# FluxR3-v3.net
KiCad netlist of a schematic drawn in EAGLE
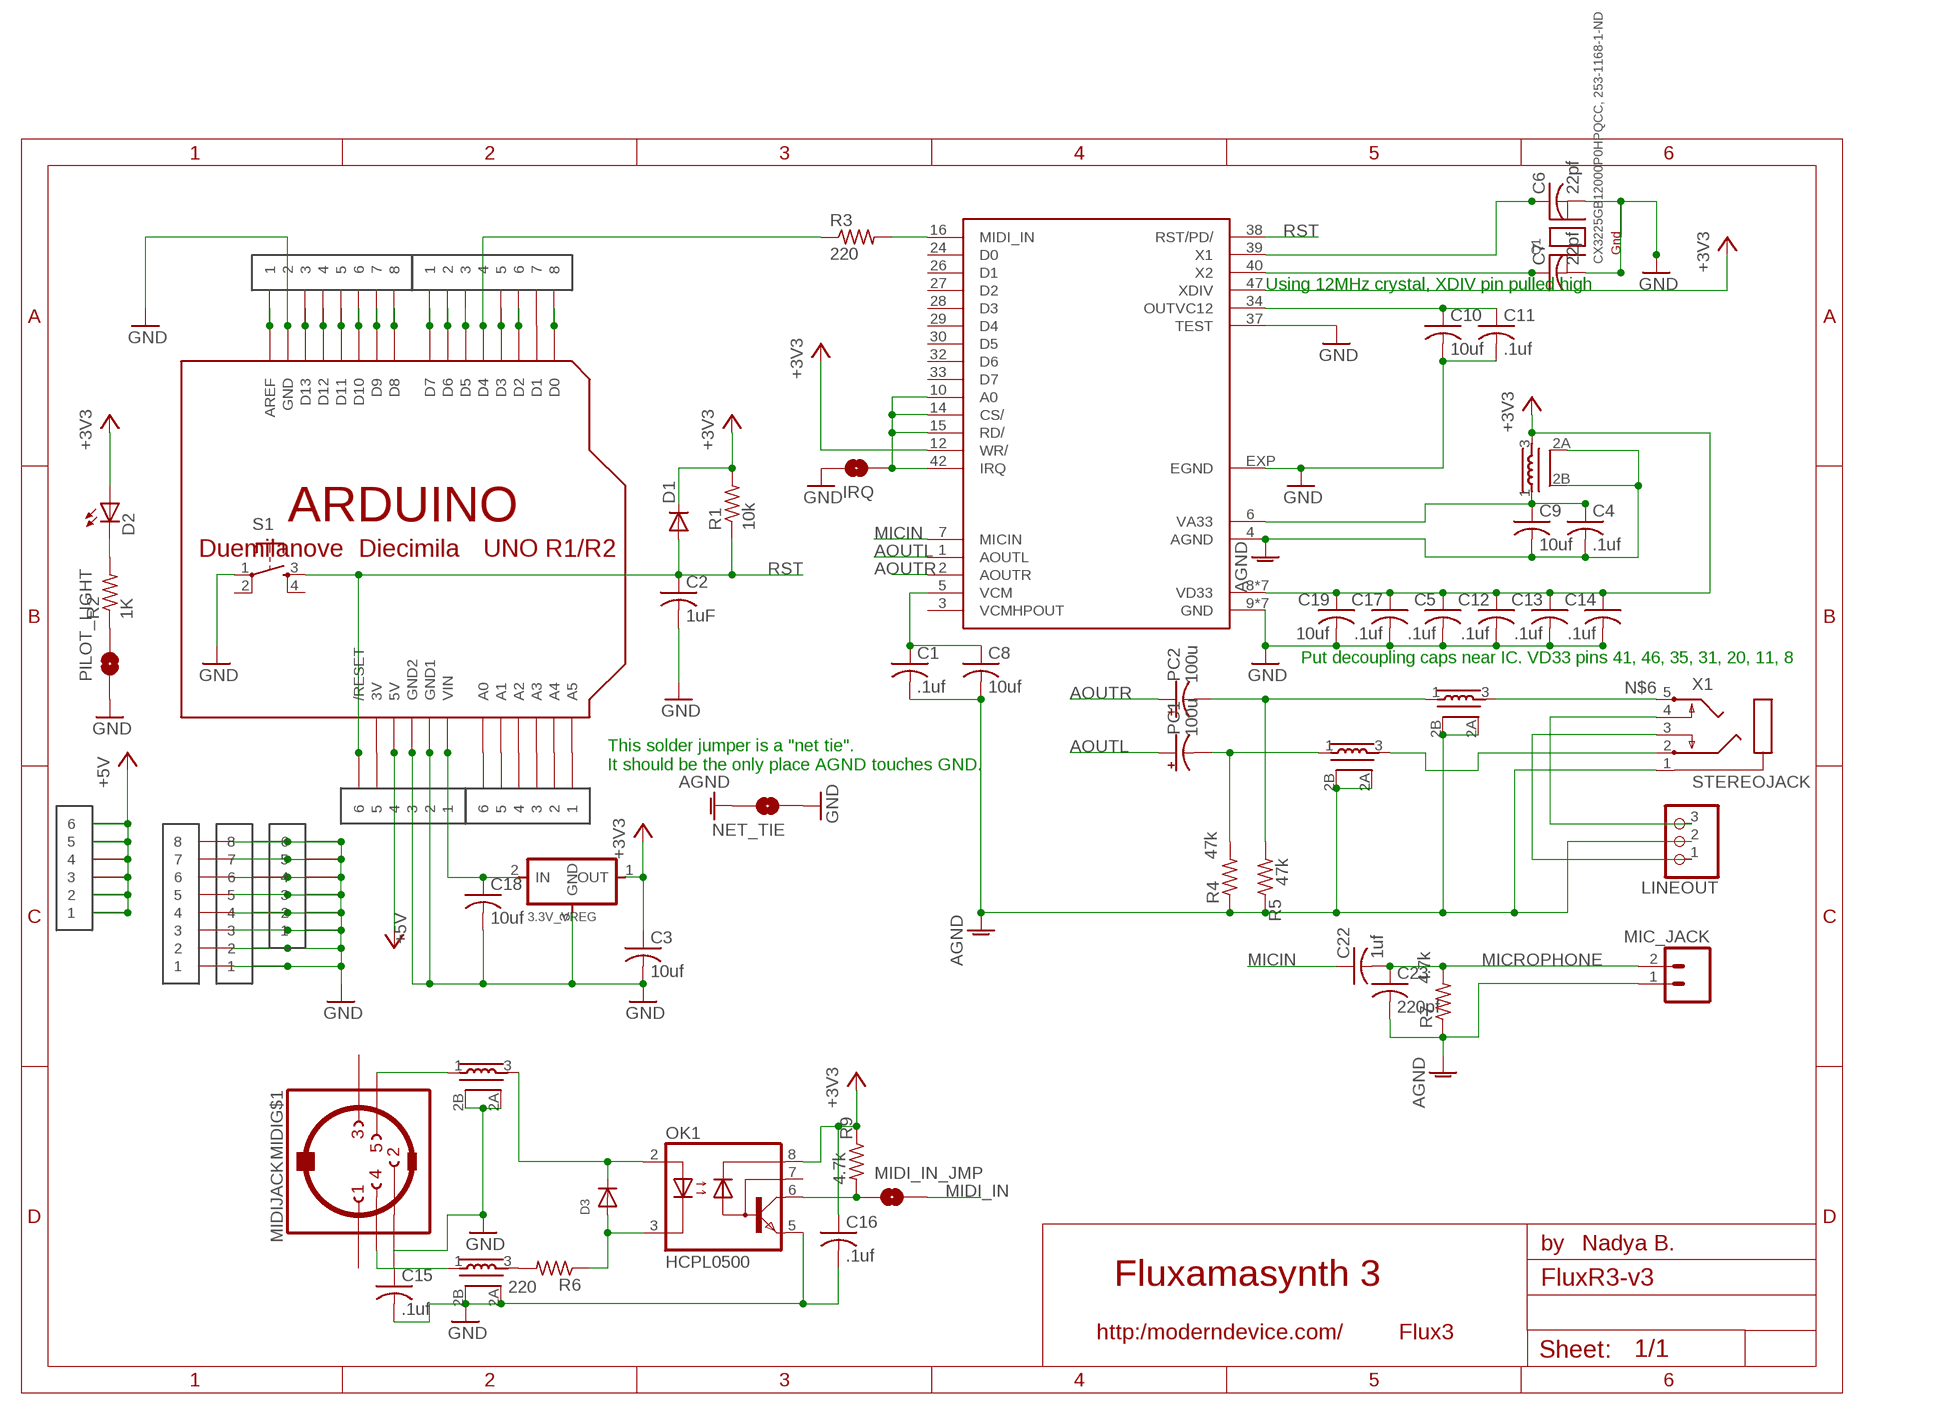
[diagram p0: schematic, sheet 1]

(export (version "E")
  (design (tool "Eeschema 10.0.6"))
  (components
    (comp (ref "3.3V_VREG")
      (value "REGULATORSOT23")
      (footprint "eagle-import:SOT23")
      (libsource (lib "eagle-import") (part "REGULATORSOT23"))
    )
    (comp (ref "ARDUINO")
      (value "ARDUINO-NOHOLE")
      (footprint "eagle-import:ARDUINO-NOHOLE")
      (libsource (lib "eagle-import") (part "ARDUINO-NOHOLE"))
    )
    (comp (ref "C1")
      (value ".1uf")
      (footprint "eagle-import:C0603K")
      (libsource (lib "eagle-import") (part "C-USC0603K"))
    )
    (comp (ref "C2")
      (value "1uF")
      (footprint "eagle-import:C0805")
      (libsource (lib "eagle-import") (part "C-USC0805"))
    )
    (comp (ref "C3")
      (value "10uf")
      (footprint "eagle-import:C0805")
      (libsource (lib "eagle-import") (part "C-USC0805"))
    )
    (comp (ref "C4")
      (value ".1uf")
      (footprint "eagle-import:C0603K")
      (libsource (lib "eagle-import") (part "C-USC0603K"))
    )
    (comp (ref "C5")
      (value ".1uf")
      (footprint "eagle-import:C0603K")
      (libsource (lib "eagle-import") (part "C-USC0603K"))
    )
    (comp (ref "C6")
      (value "22pf")
      (footprint "eagle-import:C0805")
      (libsource (lib "eagle-import") (part "C-USC0805"))
    )
    (comp (ref "C7")
      (value "22pf")
      (footprint "eagle-import:C0805")
      (libsource (lib "eagle-import") (part "C-USC0805"))
    )
    (comp (ref "C8")
      (value "10uf")
      (footprint "eagle-import:C0805")
      (libsource (lib "eagle-import") (part "C-USC0805"))
    )
    (comp (ref "C9")
      (value "10uf")
      (footprint "eagle-import:C0805")
      (libsource (lib "eagle-import") (part "C-USC0805"))
    )
    (comp (ref "C10")
      (value "10uf")
      (footprint "eagle-import:C0805")
      (libsource (lib "eagle-import") (part "C-USC0805"))
    )
    (comp (ref "C11")
      (value ".1uf")
      (footprint "eagle-import:C0603K")
      (libsource (lib "eagle-import") (part "C-USC0603K"))
    )
    (comp (ref "C12")
      (value ".1uf")
      (footprint "eagle-import:C0603K")
      (libsource (lib "eagle-import") (part "C-USC0603K"))
    )
    (comp (ref "C13")
      (value ".1uf")
      (footprint "eagle-import:C0603K")
      (libsource (lib "eagle-import") (part "C-USC0603K"))
    )
    (comp (ref "C14")
      (value ".1uf")
      (footprint "eagle-import:C0603K")
      (libsource (lib "eagle-import") (part "C-USC0603K"))
    )
    (comp (ref "C15")
      (value ".1uf")
      (footprint "eagle-import:C0805")
      (libsource (lib "eagle-import") (part "C-USC0805"))
    )
    (comp (ref "C16")
      (value ".1uf")
      (footprint "eagle-import:C0805")
      (libsource (lib "eagle-import") (part "C-USC0805"))
    )
    (comp (ref "C17")
      (value ".1uf")
      (footprint "eagle-import:C0603K")
      (libsource (lib "eagle-import") (part "C-USC0603K"))
    )
    (comp (ref "C18")
      (value "10uf")
      (footprint "eagle-import:C0805")
      (libsource (lib "eagle-import") (part "C-USC0805"))
    )
    (comp (ref "C19")
      (value "10uf")
      (footprint "eagle-import:C0805")
      (libsource (lib "eagle-import") (part "C-USC0805"))
    )
    (comp (ref "C22")
      (value "1uf")
      (footprint "eagle-import:C0805")
      (libsource (lib "eagle-import") (part "C-USC0805"))
    )
    (comp (ref "C23")
      (value "220pf")
      (footprint "eagle-import:C0805")
      (libsource (lib "eagle-import") (part "C-USC0805"))
    )
    (comp (ref "D1")
      (value "DIODESOD123")
      (footprint "eagle-import:SOD123")
      (libsource (lib "eagle-import") (part "DIODESOD123"))
    )
    (comp (ref "D2")
      (value "LED1206")
      (footprint "eagle-import:LED-1206")
      (libsource (lib "eagle-import") (part "LED1206"))
    )
    (comp (ref "D3")
      (value "DIODE_SOD-523")
      (footprint "eagle-import:SOD-523")
      (libsource (lib "eagle-import") (part "DIODE_SOD-523"))
    )
    (comp (ref "IRQ")
      (value "MODERNDEVICE_SOLDERJUMPERTRACE")
      (footprint "eagle-import:MODERNDEVICE_SJ_2S-TRACE")
      (libsource (lib "eagle-import") (part "MODERNDEVICE_SOLDERJUMPERTRACE"))
    )
    (comp (ref "LINEOUT")
      (value "PINHD-1X3")
      (footprint "eagle-import:1X03")
      (libsource (lib "eagle-import") (part "PINHD-1X3"))
    )
    (comp (ref "MIC_JACK")
      (value "M02PTH")
      (footprint "eagle-import:1X02")
      (libsource (lib "eagle-import") (part "M02PTH"))
    )
    (comp (ref "MIDI")
      (value "MIDIJACK")
      (footprint "eagle-import:CP-2350")
      (libsource (lib "eagle-import") (part "MIDIJACK"))
    )
    (comp (ref "MIDI_IN_JMP")
      (value "SOLDERJUMPERNO")
      (footprint "eagle-import:SJ_2S-NO")
      (libsource (lib "eagle-import") (part "SOLDERJUMPERNO"))
    )
    (comp (ref "NET_TIE")
      (value "MODERNDEVICE_SOLDERJUMPERTRACE")
      (footprint "eagle-import:MODERNDEVICE_SJ_2S-TRACE")
      (libsource (lib "eagle-import") (part "MODERNDEVICE_SOLDERJUMPERTRACE"))
    )
    (comp (ref "OK1")
      (value "HCPL0500")
      (footprint "eagle-import:SOIC08")
      (fields (field (name "MF") "AGILENT TECHNOLOGIES") (field (name "MPN") "HCPL-0500-000E"))
      (libsource (lib "eagle-import") (part "HCPL0500"))
    )
    (comp (ref "PC1")
      (value "100u")
      (footprint "eagle-import:PANASONIC_E")
      (libsource (lib "eagle-import") (part "CPOL-USE"))
    )
    (comp (ref "PC2")
      (value "100u")
      (footprint "eagle-import:PANASONIC_E")
      (libsource (lib "eagle-import") (part "CPOL-USE"))
    )
    (comp (ref "PILOT_LIGHT")
      (value "MODERNDEVICE_SOLDERJUMPERTRACE")
      (footprint "eagle-import:MODERNDEVICE_SJ_2S-TRACE")
      (libsource (lib "eagle-import") (part "MODERNDEVICE_SOLDERJUMPERTRACE"))
    )
    (comp (ref "Q1")
      (value "CX3225GB12000P0HPQCC, 253-1168-1-ND")
      (footprint "eagle-import:MODERNDEVICE_NX3225")
      (libsource (lib "eagle-import") (part "MODERNDEVICE_XTAL-4-3225"))
    )
    (comp (ref "R1")
      (value "10k")
      (footprint "eagle-import:M0805")
      (libsource (lib "eagle-import") (part "R-US_M0805"))
    )
    (comp (ref "R2")
      (value "1K")
      (footprint "eagle-import:M0805")
      (libsource (lib "eagle-import") (part "R-US_M0805"))
    )
    (comp (ref "R3")
      (value "220")
      (footprint "eagle-import:M0805")
      (libsource (lib "eagle-import") (part "R-US_M0805"))
    )
    (comp (ref "R4")
      (value "47k")
      (footprint "eagle-import:R0603")
      (libsource (lib "eagle-import") (part "R-US_R0603"))
    )
    (comp (ref "R5")
      (value "47k")
      (footprint "eagle-import:R0603")
      (libsource (lib "eagle-import") (part "R-US_R0603"))
    )
    (comp (ref "R6")
      (value "220")
      (footprint "eagle-import:M0805")
      (libsource (lib "eagle-import") (part "R-US_M0805"))
    )
    (comp (ref "R7")
      (value "4.7k")
      (footprint "eagle-import:M0805")
      (libsource (lib "eagle-import") (part "R-US_M0805"))
    )
    (comp (ref "R9")
      (value "4.7k")
      (footprint "eagle-import:R0603")
      (libsource (lib "eagle-import") (part "R-US_R0603"))
    )
    (comp (ref "S1")
      (value "6MM_SWITCH6MM_SWITCH")
      (footprint "eagle-import:6MM_SWITCH")
      (libsource (lib "eagle-import") (part "6MM_SWITCH6MM_SWITCH"))
    )
    (comp (ref "SAM2695")
      (value "SAM2695")
      (footprint "eagle-import:QFN48")
      (libsource (lib "eagle-import") (part "SAM2695"))
    )
    (comp (ref "U$1")
      (value "1X8_CLEAN")
      (footprint "eagle-import:1X8_CLEAN")
      (libsource (lib "eagle-import") (part "1X8_CLEAN"))
    )
    (comp (ref "U$2")
      (value "1X6_CLEAN")
      (footprint "eagle-import:1X6_CLEAN")
      (libsource (lib "eagle-import") (part "1X6_CLEAN"))
    )
    (comp (ref "U$3")
      (value "1X6_CLEAN")
      (footprint "eagle-import:1X6_CLEAN")
      (libsource (lib "eagle-import") (part "1X6_CLEAN"))
    )
    (comp (ref "U$4")
      (value "NFM21CC223R1H3D")
      (footprint "eagle-import:3PC")
      (libsource (lib "eagle-import") (part "NFM21CC223R1H3D"))
    )
    (comp (ref "U$5")
      (value "NFM21CC223R1H3D")
      (footprint "eagle-import:3PC")
      (libsource (lib "eagle-import") (part "NFM21CC223R1H3D"))
    )
    (comp (ref "U$6")
      (value "1X6_CLEAN")
      (footprint "eagle-import:1X6_CLEAN")
      (libsource (lib "eagle-import") (part "1X6_CLEAN"))
    )
    (comp (ref "U$7")
      (value "NFM21CC223R1H3D")
      (footprint "eagle-import:3PC")
      (libsource (lib "eagle-import") (part "NFM21CC223R1H3D"))
    )
    (comp (ref "U$8")
      (value "1X6_CLEAN")
      (footprint "eagle-import:1X6_CLEAN")
      (libsource (lib "eagle-import") (part "1X6_CLEAN"))
    )
    (comp (ref "U$9")
      (value "1X8_CLEAN")
      (footprint "eagle-import:1X8_CLEAN")
      (libsource (lib "eagle-import") (part "1X8_CLEAN"))
    )
    (comp (ref "U$10")
      (value "NFM21CC223R1H3D")
      (footprint "eagle-import:3PC")
      (libsource (lib "eagle-import") (part "NFM21CC223R1H3D"))
    )
    (comp (ref "U$11")
      (value "1X8_CLEAN")
      (footprint "eagle-import:1X8_CLEAN")
      (libsource (lib "eagle-import") (part "1X8_CLEAN"))
    )
    (comp (ref "U$12")
      (value "NFM21CC223R1H3D")
      (footprint "eagle-import:3PC")
      (libsource (lib "eagle-import") (part "NFM21CC223R1H3D"))
    )
    (comp (ref "U$13")
      (value "1X8_CLEAN")
      (footprint "eagle-import:1X8_CLEAN")
      (libsource (lib "eagle-import") (part "1X8_CLEAN"))
    )
    (comp (ref "X1")
      (value "STEREOJACK")
      (footprint "eagle-import:STX3100")
      (libsource (lib "eagle-import") (part "STEREOJACK"))
    )
  )
  (nets
    (net (code "1") (name "+3V3") (class "Default")
      (node (ref "3.3V_VREG") (pin "1") (pinfunction "OUT_1") (pintype "bidirectional"))
      (node (ref "C12") (pin "1") (pinfunction "1_1") (pintype "passive"))
      (node (ref "C13") (pin "1") (pinfunction "1_1") (pintype "passive"))
      (node (ref "C14") (pin "1") (pinfunction "1_1") (pintype "passive"))
      (node (ref "C16") (pin "1") (pinfunction "1_1") (pintype "passive"))
      (node (ref "C17") (pin "1") (pinfunction "1_1") (pintype "passive"))
      (node (ref "C19") (pin "1") (pinfunction "1_1") (pintype "passive"))
      (node (ref "C3") (pin "1") (pinfunction "1_1") (pintype "passive"))
      (node (ref "C5") (pin "1") (pinfunction "1_1") (pintype "passive"))
      (node (ref "D1") (pin "CATHODE") (pinfunction "C_CATHODE") (pintype "passive"))
      (node (ref "D2") (pin "A") (pinfunction "A_A") (pintype "passive"))
      (node (ref "OK1") (pin "8") (pinfunction "VCC_8") (pintype "passive"))
      (node (ref "R1") (pin "2") (pinfunction "2_2") (pintype "passive"))
      (node (ref "R9") (pin "1") (pinfunction "1_1") (pintype "passive"))
      (node (ref "SAM2695") (pin "11") (pinfunction "VD33_11") (pintype "power_in"))
      (node (ref "SAM2695") (pin "12") (pinfunction "WR/_12") (pintype "input"))
      (node (ref "SAM2695") (pin "20") (pinfunction "VD33_20") (pintype "power_in"))
      (node (ref "SAM2695") (pin "31") (pinfunction "VD33_31") (pintype "power_in"))
      (node (ref "SAM2695") (pin "35") (pinfunction "VD33_35") (pintype "power_in"))
      (node (ref "SAM2695") (pin "41") (pinfunction "VD33_41") (pintype "power_in"))
      (node (ref "SAM2695") (pin "46") (pinfunction "VD33_46") (pintype "power_in"))
      (node (ref "SAM2695") (pin "47") (pinfunction "XDIV_47") (pintype "input"))
      (node (ref "SAM2695") (pin "8") (pinfunction "VD33_8") (pintype "power_in"))
      (node (ref "U$7") (pin "3") (pinfunction "3_3") (pintype "bidirectional"))
    )
    (net (code "2") (name "+5V") (class "Default")
      (node (ref "ARDUINO") (pin "5V") (pinfunction "5V_5V") (pintype "power_in"))
      (node (ref "U$2") (pin "P$1") (pinfunction "1_P$1") (pintype "bidirectional"))
      (node (ref "U$2") (pin "P$2") (pinfunction "2_P$2") (pintype "bidirectional"))
      (node (ref "U$2") (pin "P$3") (pinfunction "3_P$3") (pintype "bidirectional"))
      (node (ref "U$2") (pin "P$4") (pinfunction "4_P$4") (pintype "bidirectional"))
      (node (ref "U$2") (pin "P$5") (pinfunction "5_P$5") (pintype "bidirectional"))
      (node (ref "U$2") (pin "P$6") (pinfunction "6_P$6") (pintype "bidirectional"))
      (node (ref "U$6") (pin "P$4") (pinfunction "4_P$4") (pintype "bidirectional"))
    )
    (net (code "3") (name "/AOUTL") (class "Default")
      (node (ref "PC1") (pin "+") (pinfunction "+_+") (pintype "passive"))
      (node (ref "SAM2695") (pin "1") (pinfunction "AOUTL_1") (pintype "output"))
    )
    (net (code "4") (name "/AOUTR") (class "Default")
      (node (ref "PC2") (pin "+") (pinfunction "+_+") (pintype "passive"))
      (node (ref "SAM2695") (pin "2") (pinfunction "AOUTR_2") (pintype "output"))
    )
    (net (code "5") (name "/MICIN") (class "Default")
      (node (ref "C22") (pin "1") (pinfunction "1_1") (pintype "passive"))
      (node (ref "SAM2695") (pin "7") (pinfunction "MICIN_7") (pintype "input"))
    )
    (net (code "6") (name "/MICROPHONE") (class "Default")
      (node (ref "C22") (pin "2") (pinfunction "2_2") (pintype "passive"))
      (node (ref "C23") (pin "1") (pinfunction "1_1") (pintype "passive"))
      (node (ref "MIC_JACK") (pin "2") (pinfunction "2_2") (pintype "passive"))
      (node (ref "R7") (pin "2") (pinfunction "2_2") (pintype "passive"))
    )
    (net (code "7") (name "/MIDI_FROM_ARDUINO") (class "Default")
      (node (ref "ARDUINO") (pin "D4") (pinfunction "D4_D4") (pintype "bidirectional"))
      (node (ref "MIDI_IN_JMP") (pin "1") (pinfunction "1_1") (pintype "passive"))
      (node (ref "OK1") (pin "6") (pinfunction "VO_6") (pintype "passive"))
      (node (ref "R3") (pin "1") (pinfunction "1_1") (pintype "passive"))
      (node (ref "R9") (pin "2") (pinfunction "2_2") (pintype "passive"))
      (node (ref "U$9") (pin "P$4") (pinfunction "4_P$4") (pintype "bidirectional"))
    )
    (net (code "8") (name "/MIDI_IN") (class "Default")
      (node (ref "MIDI_IN_JMP") (pin "2") (pinfunction "2_2") (pintype "passive"))
      (node (ref "R3") (pin "2") (pinfunction "2_2") (pintype "passive"))
      (node (ref "SAM2695") (pin "16") (pinfunction "MIDI_IN_16") (pintype "input"))
    )
    (net (code "9") (name "/N$6") (class "Default")
      (node (ref "U$4") (pin "3") (pinfunction "3_3") (pintype "bidirectional"))
      (node (ref "X1") (pin "5") (pinfunction "5_5") (pintype "passive"))
    )
    (net (code "10") (name "/RST") (class "Default")
      (node (ref "ARDUINO") (pin "RESET") (pinfunction "/RESET_RESET") (pintype "bidirectional"))
      (node (ref "C2") (pin "1") (pinfunction "1_1") (pintype "passive"))
      (node (ref "D1") (pin "ANODE") (pinfunction "A_ANODE") (pintype "passive"))
      (node (ref "R1") (pin "1") (pinfunction "1_1") (pintype "passive"))
      (node (ref "S1") (pin "3") (pinfunction "S_3") (pintype "passive"))
      (node (ref "SAM2695") (pin "38") (pinfunction "RST/PD/_38") (pintype "input"))
      (node (ref "U$6") (pin "P$6") (pinfunction "6_P$6") (pintype "bidirectional"))
    )
    (net (code "11") (name "AGND") (class "Default")
      (node (ref "C1") (pin "2") (pinfunction "2_2") (pintype "passive"))
      (node (ref "C23") (pin "2") (pinfunction "2_2") (pintype "passive"))
      (node (ref "C4") (pin "2") (pinfunction "2_2") (pintype "passive"))
      (node (ref "C8") (pin "2") (pinfunction "2_2") (pintype "passive"))
      (node (ref "C9") (pin "2") (pinfunction "2_2") (pintype "passive"))
      (node (ref "LINEOUT") (pin "2") (pinfunction "2_2") (pintype "passive"))
      (node (ref "MIC_JACK") (pin "1") (pinfunction "1_1") (pintype "passive"))
      (node (ref "NET_TIE") (pin "2") (pinfunction "2_2") (pintype "passive"))
      (node (ref "R4") (pin "1") (pinfunction "1_1") (pintype "passive"))
      (node (ref "R5") (pin "1") (pinfunction "1_1") (pintype "passive"))
      (node (ref "R7") (pin "1") (pinfunction "1_1") (pintype "passive"))
      (node (ref "SAM2695") (pin "4") (pinfunction "AGND_4") (pintype "power_in"))
      (node (ref "U$4") (pin "2A") (pinfunction "2A_2A") (pintype "power_in"))
      (node (ref "U$4") (pin "2B") (pinfunction "2B_2B") (pintype "power_in"))
      (node (ref "U$5") (pin "2A") (pinfunction "2A_2A") (pintype "power_in"))
      (node (ref "U$5") (pin "2B") (pinfunction "2B_2B") (pintype "power_in"))
      (node (ref "U$7") (pin "2A") (pinfunction "2A_2A") (pintype "power_in"))
      (node (ref "U$7") (pin "2B") (pinfunction "2B_2B") (pintype "power_in"))
      (node (ref "X1") (pin "1") (pinfunction "1_1") (pintype "passive"))
    )
    (net (code "12") (name "GND") (class "Default")
      (node (ref "3.3V_VREG") (pin "3") (pinfunction "GND_3") (pintype "bidirectional"))
      (node (ref "ARDUINO") (pin "GND") (pinfunction "GND_GND") (pintype "power_in"))
      (node (ref "ARDUINO") (pin "GND1") (pinfunction "GND1_GND1") (pintype "power_in"))
      (node (ref "ARDUINO") (pin "GND2") (pinfunction "GND2_GND2") (pintype "power_in"))
      (node (ref "C10") (pin "2") (pinfunction "2_2") (pintype "passive"))
      (node (ref "C11") (pin "2") (pinfunction "2_2") (pintype "passive"))
      (node (ref "C12") (pin "2") (pinfunction "2_2") (pintype "passive"))
      (node (ref "C13") (pin "2") (pinfunction "2_2") (pintype "passive"))
      (node (ref "C14") (pin "2") (pinfunction "2_2") (pintype "passive"))
      (node (ref "C15") (pin "2") (pinfunction "2_2") (pintype "passive"))
      (node (ref "C16") (pin "2") (pinfunction "2_2") (pintype "passive"))
      (node (ref "C17") (pin "2") (pinfunction "2_2") (pintype "passive"))
      (node (ref "C18") (pin "2") (pinfunction "2_2") (pintype "passive"))
      (node (ref "C19") (pin "2") (pinfunction "2_2") (pintype "passive"))
      (node (ref "C2") (pin "2") (pinfunction "2_2") (pintype "passive"))
      (node (ref "C3") (pin "2") (pinfunction "2_2") (pintype "passive"))
      (node (ref "C5") (pin "2") (pinfunction "2_2") (pintype "passive"))
      (node (ref "C6") (pin "2") (pinfunction "2_2") (pintype "passive"))
      (node (ref "C7") (pin "2") (pinfunction "2_2") (pintype "passive"))
      (node (ref "IRQ") (pin "2") (pinfunction "2_2") (pintype "passive"))
      (node (ref "NET_TIE") (pin "1") (pinfunction "1_1") (pintype "passive"))
      (node (ref "OK1") (pin "5") (pinfunction "GND_5") (pintype "passive"))
      (node (ref "PILOT_LIGHT") (pin "1") (pinfunction "1_1") (pintype "passive"))
      (node (ref "Q1") (pin "2") (pinfunction "G2_2") (pintype "power_in"))
      (node (ref "Q1") (pin "4") (pinfunction "G1_4") (pintype "power_in"))
      (node (ref "S1") (pin "1") (pinfunction "P_1") (pintype "passive"))
      (node (ref "SAM2695") (pin "13") (pinfunction "GND_13") (pintype "power_in"))
      (node (ref "SAM2695") (pin "18") (pinfunction "GND_18") (pintype "power_in"))
      (node (ref "SAM2695") (pin "25") (pinfunction "GND_25") (pintype "power_in"))
      (node (ref "SAM2695") (pin "36") (pinfunction "GND_36") (pintype "power_in"))
      (node (ref "SAM2695") (pin "37") (pinfunction "TEST_37") (pintype "input"))
      (node (ref "SAM2695") (pin "45") (pinfunction "GND_45") (pintype "power_in"))
      (node (ref "SAM2695") (pin "48") (pinfunction "GND_48") (pintype "power_in"))
      (node (ref "SAM2695") (pin "9") (pinfunction "GND_9") (pintype "power_in"))
      (node (ref "SAM2695") (pin "EXP") (pinfunction "EGND_EXP") (pintype "power_in"))
      (node (ref "U$1") (pin "P$1") (pinfunction "1_P$1") (pintype "bidirectional"))
      (node (ref "U$1") (pin "P$2") (pinfunction "2_P$2") (pintype "bidirectional"))
      (node (ref "U$1") (pin "P$3") (pinfunction "3_P$3") (pintype "bidirectional"))
      (node (ref "U$1") (pin "P$4") (pinfunction "4_P$4") (pintype "bidirectional"))
      (node (ref "U$1") (pin "P$5") (pinfunction "5_P$5") (pintype "bidirectional"))
      (node (ref "U$1") (pin "P$6") (pinfunction "6_P$6") (pintype "bidirectional"))
      (node (ref "U$1") (pin "P$7") (pinfunction "7_P$7") (pintype "bidirectional"))
      (node (ref "U$1") (pin "P$8") (pinfunction "8_P$8") (pintype "bidirectional"))
      (node (ref "U$10") (pin "2A") (pinfunction "2A_2A") (pintype "power_in"))
      (node (ref "U$10") (pin "2B") (pinfunction "2B_2B") (pintype "power_in"))
      (node (ref "U$11") (pin "P$1") (pinfunction "1_P$1") (pintype "bidirectional"))
      (node (ref "U$11") (pin "P$2") (pinfunction "2_P$2") (pintype "bidirectional"))
      (node (ref "U$11") (pin "P$3") (pinfunction "3_P$3") (pintype "bidirectional"))
      (node (ref "U$11") (pin "P$4") (pinfunction "4_P$4") (pintype "bidirectional"))
      (node (ref "U$11") (pin "P$5") (pinfunction "5_P$5") (pintype "bidirectional"))
      (node (ref "U$11") (pin "P$6") (pinfunction "6_P$6") (pintype "bidirectional"))
      (node (ref "U$11") (pin "P$7") (pinfunction "7_P$7") (pintype "bidirectional"))
      (node (ref "U$11") (pin "P$8") (pinfunction "8_P$8") (pintype "bidirectional"))
      (node (ref "U$12") (pin "2A") (pinfunction "2A_2A") (pintype "power_in"))
      (node (ref "U$12") (pin "2B") (pinfunction "2B_2B") (pintype "power_in"))
      (node (ref "U$13") (pin "P$2") (pinfunction "2_P$2") (pintype "bidirectional"))
      (node (ref "U$3") (pin "P$1") (pinfunction "1_P$1") (pintype "bidirectional"))
      (node (ref "U$3") (pin "P$2") (pinfunction "2_P$2") (pintype "bidirectional"))
      (node (ref "U$3") (pin "P$3") (pinfunction "3_P$3") (pintype "bidirectional"))
      (node (ref "U$3") (pin "P$4") (pinfunction "4_P$4") (pintype "bidirectional"))
      (node (ref "U$3") (pin "P$5") (pinfunction "5_P$5") (pintype "bidirectional"))
      (node (ref "U$3") (pin "P$6") (pinfunction "6_P$6") (pintype "bidirectional"))
      (node (ref "U$6") (pin "P$2") (pinfunction "2_P$2") (pintype "bidirectional"))
      (node (ref "U$6") (pin "P$3") (pinfunction "3_P$3") (pintype "bidirectional"))
    )
    (net (code "13") (name "Net-(3.3V_VREG-IN)") (class "Default")
      (node (ref "3.3V_VREG") (pin "2") (pinfunction "IN_2") (pintype "bidirectional"))
      (node (ref "ARDUINO") (pin "VIN") (pinfunction "VIN_VIN") (pintype "power_in"))
      (node (ref "C18") (pin "1") (pinfunction "1_1") (pintype "passive"))
      (node (ref "U$6") (pin "P$1") (pinfunction "1_P$1") (pintype "bidirectional"))
    )
    (net (code "14") (name "Net-(C15-Pad1)") (class "Default")
      (node (ref "C15") (pin "1") (pinfunction "1_1") (pintype "passive"))
      (node (ref "MIDI") (pin "2") (pinfunction "2_2") (pintype "passive"))
    )
    (net (code "15") (name "Net-(D2-PadC)") (class "Default")
      (node (ref "D2") (pin "C") (pinfunction "C_C") (pintype "passive"))
      (node (ref "R2") (pin "2") (pinfunction "2_2") (pintype "passive"))
    )
    (net (code "16") (name "Net-(D3-C)") (class "Default")
      (node (ref "D3") (pin "K") (pinfunction "C_K") (pintype "passive"))
      (node (ref "OK1") (pin "2") (pinfunction "A_2") (pintype "passive"))
      (node (ref "U$12") (pin "3") (pinfunction "3_3") (pintype "bidirectional"))
    )
    (net (code "17") (name "Net-(LINEOUT-Pad1)") (class "Default")
      (node (ref "LINEOUT") (pin "1") (pinfunction "1_1") (pintype "passive"))
      (node (ref "X1") (pin "3") (pinfunction "3_3") (pintype "passive"))
    )
    (net (code "18") (name "Net-(LINEOUT-Pad3)") (class "Default")
      (node (ref "LINEOUT") (pin "3") (pinfunction "3_3") (pintype "passive"))
      (node (ref "X1") (pin "4") (pinfunction "4_4") (pintype "passive"))
    )
    (net (code "19") (name "Net-(MIDI-Pad4)") (class "Default")
      (node (ref "MIDI") (pin "4") (pinfunction "4_4") (pintype "passive"))
      (node (ref "U$10") (pin "1") (pinfunction "1_1") (pintype "bidirectional"))
    )
    (net (code "20") (name "Net-(MIDI-Pad5)") (class "Default")
      (node (ref "MIDI") (pin "5") (pinfunction "5_5") (pintype "passive"))
      (node (ref "U$12") (pin "1") (pinfunction "1_1") (pintype "bidirectional"))
    )
    (net (code "21") (name "Net-(OK1-C)") (class "Default")
      (node (ref "D3") (pin "A") (pinfunction "A_A") (pintype "passive"))
      (node (ref "OK1") (pin "3") (pinfunction "C_3") (pintype "passive"))
      (node (ref "R6") (pin "1") (pinfunction "1_1") (pintype "passive"))
    )
    (net (code "22") (name "Net-(PC1-Pad-)") (class "Default")
      (node (ref "PC1") (pin "-") (pinfunction "-_-") (pintype "passive"))
      (node (ref "R4") (pin "2") (pinfunction "2_2") (pintype "passive"))
      (node (ref "U$5") (pin "1") (pinfunction "1_1") (pintype "bidirectional"))
    )
    (net (code "23") (name "Net-(PC2-Pad-)") (class "Default")
      (node (ref "PC2") (pin "-") (pinfunction "-_-") (pintype "passive"))
      (node (ref "R5") (pin "2") (pinfunction "2_2") (pintype "passive"))
      (node (ref "U$4") (pin "1") (pinfunction "1_1") (pintype "bidirectional"))
    )
    (net (code "24") (name "Net-(PILOT_LIGHT-Pad2)") (class "Default")
      (node (ref "PILOT_LIGHT") (pin "2") (pinfunction "2_2") (pintype "passive"))
      (node (ref "R2") (pin "1") (pinfunction "1_1") (pintype "passive"))
    )
    (net (code "25") (name "Net-(R6-Pad2)") (class "Default")
      (node (ref "R6") (pin "2") (pinfunction "2_2") (pintype "passive"))
      (node (ref "U$10") (pin "3") (pinfunction "3_3") (pintype "bidirectional"))
    )
    (net (code "26") (name "Net-(SAM2695-A0)") (class "Default")
      (node (ref "IRQ") (pin "1") (pinfunction "1_1") (pintype "passive"))
      (node (ref "SAM2695") (pin "10") (pinfunction "A0_10") (pintype "input"))
      (node (ref "SAM2695") (pin "14") (pinfunction "CS/_14") (pintype "input"))
      (node (ref "SAM2695") (pin "15") (pinfunction "RD/_15") (pintype "input"))
      (node (ref "SAM2695") (pin "42") (pinfunction "IRQ_42") (pintype "output"))
    )
    (net (code "27") (name "Net-(SAM2695-OUTVC12)") (class "Default")
      (node (ref "C10") (pin "1") (pinfunction "1_1") (pintype "passive"))
      (node (ref "C11") (pin "1") (pinfunction "1_1") (pintype "passive"))
      (node (ref "SAM2695") (pin "34") (pinfunction "OUTVC12_34") (pintype "power_in"))
    )
    (net (code "28") (name "Net-(SAM2695-VA33)") (class "Default")
      (node (ref "C4") (pin "1") (pinfunction "1_1") (pintype "passive"))
      (node (ref "C9") (pin "1") (pinfunction "1_1") (pintype "passive"))
      (node (ref "SAM2695") (pin "6") (pinfunction "VA33_6") (pintype "power_in"))
      (node (ref "U$7") (pin "1") (pinfunction "1_1") (pintype "bidirectional"))
    )
    (net (code "29") (name "Net-(SAM2695-VCM)") (class "Default")
      (node (ref "C1") (pin "1") (pinfunction "1_1") (pintype "passive"))
      (node (ref "C8") (pin "1") (pinfunction "1_1") (pintype "passive"))
      (node (ref "SAM2695") (pin "5") (pinfunction "VCM_5") (pintype "output"))
    )
    (net (code "30") (name "Net-(SAM2695-X1)") (class "Default")
      (node (ref "C6") (pin "1") (pinfunction "1_1") (pintype "passive"))
      (node (ref "SAM2695") (pin "39") (pinfunction "X1_39") (pintype "bidirectional"))
    )
    (net (code "31") (name "Net-(SAM2695-X2)") (class "Default")
      (node (ref "C7") (pin "1") (pinfunction "1_1") (pintype "passive"))
      (node (ref "SAM2695") (pin "40") (pinfunction "X2_40") (pintype "bidirectional"))
    )
    (net (code "32") (name "Net-(U$5-Pad3)") (class "Default")
      (node (ref "U$5") (pin "3") (pinfunction "3_3") (pintype "bidirectional"))
      (node (ref "X1") (pin "2") (pinfunction "2_2") (pintype "passive"))
    )
    (net (code "33") (name "Net-(U$6-5)") (class "Default")
      (node (ref "ARDUINO") (pin "3V") (pinfunction "3V_3V") (pintype "power_in"))
      (node (ref "U$6") (pin "P$5") (pinfunction "5_P$5") (pintype "bidirectional"))
    )
    (net (code "34") (name "Net-(U$8-1)") (class "Default")
      (node (ref "ARDUINO") (pin "A5") (pinfunction "A5_A5") (pintype "bidirectional"))
      (node (ref "U$8") (pin "P$1") (pinfunction "1_P$1") (pintype "bidirectional"))
    )
    (net (code "35") (name "Net-(U$8-2)") (class "Default")
      (node (ref "ARDUINO") (pin "A4") (pinfunction "A4_A4") (pintype "bidirectional"))
      (node (ref "U$8") (pin "P$2") (pinfunction "2_P$2") (pintype "bidirectional"))
    )
    (net (code "36") (name "Net-(U$8-3)") (class "Default")
      (node (ref "ARDUINO") (pin "A3") (pinfunction "A3_A3") (pintype "bidirectional"))
      (node (ref "U$8") (pin "P$3") (pinfunction "3_P$3") (pintype "bidirectional"))
    )
    (net (code "37") (name "Net-(U$8-4)") (class "Default")
      (node (ref "ARDUINO") (pin "A2") (pinfunction "A2_A2") (pintype "bidirectional"))
      (node (ref "U$8") (pin "P$4") (pinfunction "4_P$4") (pintype "bidirectional"))
    )
    (net (code "38") (name "Net-(U$8-5)") (class "Default")
      (node (ref "ARDUINO") (pin "A1") (pinfunction "A1_A1") (pintype "bidirectional"))
      (node (ref "U$8") (pin "P$5") (pinfunction "5_P$5") (pintype "bidirectional"))
    )
    (net (code "39") (name "Net-(U$8-6)") (class "Default")
      (node (ref "ARDUINO") (pin "A0") (pinfunction "A0_A0") (pintype "bidirectional"))
      (node (ref "U$8") (pin "P$6") (pinfunction "6_P$6") (pintype "bidirectional"))
    )
    (net (code "40") (name "Net-(U$9-1)") (class "Default")
      (node (ref "ARDUINO") (pin "D7") (pinfunction "D7_D7") (pintype "bidirectional"))
      (node (ref "U$9") (pin "P$1") (pinfunction "1_P$1") (pintype "bidirectional"))
    )
    (net (code "41") (name "Net-(U$9-2)") (class "Default")
      (node (ref "ARDUINO") (pin "D6") (pinfunction "D6_D6") (pintype "bidirectional"))
      (node (ref "U$9") (pin "P$2") (pinfunction "2_P$2") (pintype "bidirectional"))
    )
    (net (code "42") (name "Net-(U$9-3)") (class "Default")
      (node (ref "ARDUINO") (pin "D5") (pinfunction "D5_D5") (pintype "bidirectional"))
      (node (ref "U$9") (pin "P$3") (pinfunction "3_P$3") (pintype "bidirectional"))
    )
    (net (code "43") (name "Net-(U$9-5)") (class "Default")
      (node (ref "ARDUINO") (pin "D3") (pinfunction "D3_D3") (pintype "bidirectional"))
      (node (ref "U$9") (pin "P$5") (pinfunction "5_P$5") (pintype "bidirectional"))
    )
    (net (code "44") (name "Net-(U$9-6)") (class "Default")
      (node (ref "ARDUINO") (pin "D2") (pinfunction "D2_D2") (pintype "bidirectional"))
      (node (ref "U$9") (pin "P$6") (pinfunction "6_P$6") (pintype "bidirectional"))
    )
    (net (code "45") (name "Net-(U$9-7)") (class "Default")
      (node (ref "ARDUINO") (pin "D1") (pinfunction "D1_D1") (pintype "bidirectional"))
      (node (ref "U$9") (pin "P$7") (pinfunction "7_P$7") (pintype "bidirectional"))
    )
    (net (code "46") (name "Net-(U$9-8)") (class "Default")
      (node (ref "ARDUINO") (pin "D0") (pinfunction "D0_D0") (pintype "bidirectional"))
      (node (ref "U$9") (pin "P$8") (pinfunction "8_P$8") (pintype "bidirectional"))
    )
    (net (code "47") (name "Net-(U$13-1)") (class "Default")
      (node (ref "ARDUINO") (pin "AREF") (pinfunction "AREF_AREF") (pintype "bidirectional"))
      (node (ref "U$13") (pin "P$1") (pinfunction "1_P$1") (pintype "bidirectional"))
    )
    (net (code "48") (name "Net-(U$13-3)") (class "Default")
      (node (ref "ARDUINO") (pin "D13") (pinfunction "D13_D13") (pintype "bidirectional"))
      (node (ref "U$13") (pin "P$3") (pinfunction "3_P$3") (pintype "bidirectional"))
    )
    (net (code "49") (name "Net-(U$13-4)") (class "Default")
      (node (ref "ARDUINO") (pin "D12") (pinfunction "D12_D12") (pintype "bidirectional"))
      (node (ref "U$13") (pin "P$4") (pinfunction "4_P$4") (pintype "bidirectional"))
    )
    (net (code "50") (name "Net-(U$13-5)") (class "Default")
      (node (ref "ARDUINO") (pin "D11") (pinfunction "D11_D11") (pintype "bidirectional"))
      (node (ref "U$13") (pin "P$5") (pinfunction "5_P$5") (pintype "bidirectional"))
    )
    (net (code "51") (name "Net-(U$13-6)") (class "Default")
      (node (ref "ARDUINO") (pin "D10") (pinfunction "D10_D10") (pintype "bidirectional"))
      (node (ref "U$13") (pin "P$6") (pinfunction "6_P$6") (pintype "bidirectional"))
    )
    (net (code "52") (name "Net-(U$13-7)") (class "Default")
      (node (ref "ARDUINO") (pin "D9") (pinfunction "D9_D9") (pintype "bidirectional"))
      (node (ref "U$13") (pin "P$7") (pinfunction "7_P$7") (pintype "bidirectional"))
    )
    (net (code "53") (name "Net-(U$13-8)") (class "Default")
      (node (ref "ARDUINO") (pin "D8") (pinfunction "D8_D8") (pintype "bidirectional"))
      (node (ref "U$13") (pin "P$8") (pinfunction "8_P$8") (pintype "bidirectional"))
    )
    (net (code "54") (name "unconnected-(MIDI-Pad1)") (class "Default")
      (node (ref "MIDI") (pin "1") (pinfunction "1_1") (pintype "passive"))
    )
    (net (code "55") (name "unconnected-(MIDI-Pad3)") (class "Default")
      (node (ref "MIDI") (pin "3") (pinfunction "3_3") (pintype "passive"))
    )
    (net (code "56") (name "unconnected-(OK1-VB-Pad7)") (class "Default")
      (node (ref "OK1") (pin "7") (pinfunction "VB_7") (pintype "passive"))
    )
    (net (code "57") (name "unconnected-(Q1-X1-Pad1)") (class "Default")
      (node (ref "Q1") (pin "1") (pinfunction "X1_1") (pintype "bidirectional"))
    )
    (net (code "58") (name "unconnected-(Q1-X2-Pad3)") (class "Default")
      (node (ref "Q1") (pin "3") (pinfunction "X2_3") (pintype "bidirectional"))
    )
    (net (code "59") (name "unconnected-(S1-P1-Pad2)") (class "Default")
      (node (ref "S1") (pin "2") (pinfunction "P1_2") (pintype "passive"))
    )
    (net (code "60") (name "unconnected-(S1-S1-Pad4)") (class "Default")
      (node (ref "S1") (pin "4") (pinfunction "S1_4") (pintype "passive"))
    )
    (net (code "61") (name "unconnected-(SAM2695-D0-Pad24)") (class "Default")
      (node (ref "SAM2695") (pin "24") (pinfunction "D0_24") (pintype "bidirectional"))
    )
    (net (code "62") (name "unconnected-(SAM2695-D1-Pad26)") (class "Default")
      (node (ref "SAM2695") (pin "26") (pinfunction "D1_26") (pintype "bidirectional"))
    )
    (net (code "63") (name "unconnected-(SAM2695-D2-Pad27)") (class "Default")
      (node (ref "SAM2695") (pin "27") (pinfunction "D2_27") (pintype "bidirectional"))
    )
    (net (code "64") (name "unconnected-(SAM2695-D3-Pad28)") (class "Default")
      (node (ref "SAM2695") (pin "28") (pinfunction "D3_28") (pintype "bidirectional"))
    )
    (net (code "65") (name "unconnected-(SAM2695-D4-Pad29)") (class "Default")
      (node (ref "SAM2695") (pin "29") (pinfunction "D4_29") (pintype "bidirectional"))
    )
    (net (code "66") (name "unconnected-(SAM2695-D5-Pad30)") (class "Default")
      (node (ref "SAM2695") (pin "30") (pinfunction "D5_30") (pintype "bidirectional"))
    )
    (net (code "67") (name "unconnected-(SAM2695-D6-Pad32)") (class "Default")
      (node (ref "SAM2695") (pin "32") (pinfunction "D6_32") (pintype "bidirectional"))
    )
    (net (code "68") (name "unconnected-(SAM2695-D7-Pad33)") (class "Default")
      (node (ref "SAM2695") (pin "33") (pinfunction "D7_33") (pintype "bidirectional"))
    )
    (net (code "69") (name "unconnected-(SAM2695-VCMHPOUT-Pad3)") (class "Default")
      (node (ref "SAM2695") (pin "3") (pinfunction "VCMHPOUT_3") (pintype "output"))
    )
  )
)
